# New_rev2.net
KiCad netlist of a schematic drawn in EAGLE
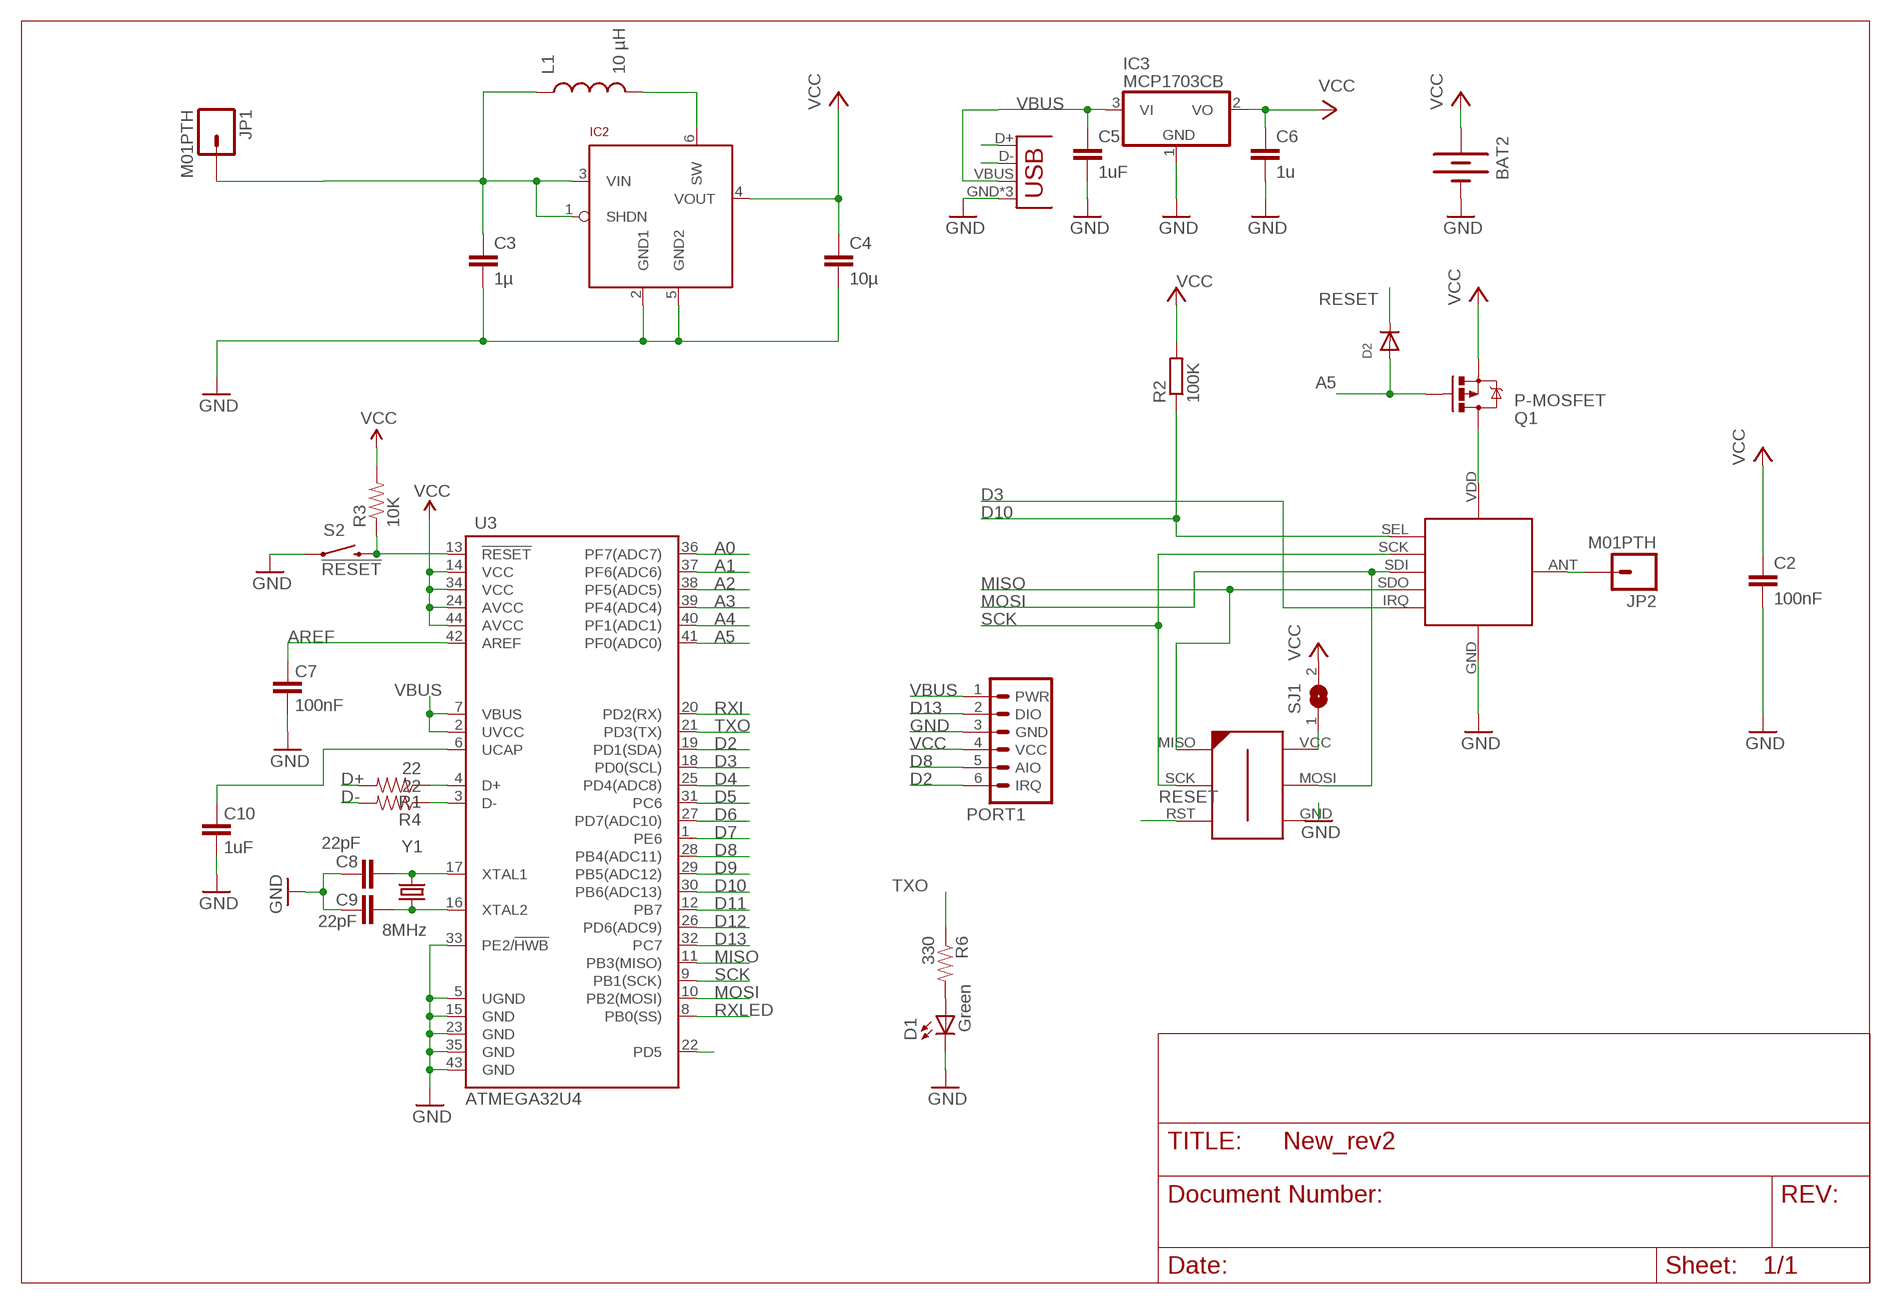
[diagram p0: schematic, sheet 1]

(export (version "E")
  (design (tool "Eeschema 10.0.6"))
  (components
    (comp (ref "BAT2")
      (value "BATTERY20PTH")
      (footprint "eagle-import:BATTCOM_20MM_PTH")
      (libsource (lib "eagle-import") (part "BATTERY20PTH"))
    )
    (comp (ref "C2")
      (value "100nF")
      (footprint "eagle-import:C0603K")
      (libsource (lib "eagle-import") (part "C-EUC0603K"))
    )
    (comp (ref "C3")
      (value "1µ")
      (footprint "eagle-import:0603-CAP")
      (libsource (lib "eagle-import") (part "CAP0603-CAP"))
    )
    (comp (ref "C4")
      (value "10µ")
      (footprint "eagle-import:0805")
      (libsource (lib "eagle-import") (part "CAP0805"))
    )
    (comp (ref "C5")
      (value "1uF")
      (footprint "eagle-import:C0603K")
      (libsource (lib "eagle-import") (part "C-EUC0603K"))
    )
    (comp (ref "C6")
      (value "1u")
      (footprint "eagle-import:C0603K")
      (libsource (lib "eagle-import") (part "C-EUC0603K"))
    )
    (comp (ref "C7")
      (value "100nF")
      (footprint "eagle-import:0402-CAP")
      (libsource (lib "eagle-import") (part "CAP0402-CAP"))
    )
    (comp (ref "C8")
      (value "22pF")
      (footprint "eagle-import:0402-CAP")
      (libsource (lib "eagle-import") (part "CAP0402-CAP"))
    )
    (comp (ref "C9")
      (value "22pF")
      (footprint "eagle-import:0402-CAP")
      (libsource (lib "eagle-import") (part "CAP0402-CAP"))
    )
    (comp (ref "C10")
      (value "1uF")
      (footprint "eagle-import:0402-CAP")
      (libsource (lib "eagle-import") (part "CAP0402-CAP"))
    )
    (comp (ref "D1")
      (value "Green")
      (footprint "eagle-import:LED-0603")
      (libsource (lib "eagle-import") (part "LED0603"))
    )
    (comp (ref "D2")
      (value "DIODESOD-323F")
      (footprint "eagle-import:SOD-323F")
      (libsource (lib "eagle-import") (part "DIODESOD-323F"))
    )
    (comp (ref "IC2")
      (value "LTC3525")
      (footprint "eagle-import:SC70")
      (libsource (lib "eagle-import") (part "LTC3525"))
    )
    (comp (ref "IC3")
      (value "MCP1703CB")
      (footprint "eagle-import:SOT23")
      (libsource (lib "eagle-import") (part "MCP1703CB"))
    )
    (comp (ref "JP1")
      (value "M01PTH")
      (footprint "eagle-import:1X01")
      (libsource (lib "eagle-import") (part "M01PTH"))
    )
    (comp (ref "JP2")
      (value "M01PTH")
      (footprint "eagle-import:1X01")
      (libsource (lib "eagle-import") (part "M01PTH"))
    )
    (comp (ref "JP3")
      (value "USB-MICROB")
      (footprint "eagle-import:USB-MICROB")
      (libsource (lib "eagle-import") (part "USB-MICROB"))
    )
    (comp (ref "L1")
      (value "10 µH")
      (footprint "eagle-import:1210")
      (libsource (lib "eagle-import") (part "INDUCTOR1210"))
    )
    (comp (ref "PORT1")
      (value "JEEPORT-FEMALE")
      (footprint "eagle-import:1X06_FEMALE_LOCK.010")
      (libsource (lib "eagle-import") (part "JEEPORT-FEMALE"))
    )
    (comp (ref "Q1")
      (value "P-MOSFET")
      (footprint "eagle-import:SOT23")
      (libsource (lib "eagle-import") (part "MOSFET-PCHANNEL"))
    )
    (comp (ref "R1")
      (value "22")
      (footprint "eagle-import:0402-RES")
      (libsource (lib "eagle-import") (part "RESISTOR0402-RES"))
    )
    (comp (ref "R2")
      (value "100K")
      (footprint "eagle-import:R0402")
      (libsource (lib "eagle-import") (part "R-EU_R0402"))
    )
    (comp (ref "R3")
      (value "10K")
      (footprint "eagle-import:0402-RES")
      (libsource (lib "eagle-import") (part "RESISTOR0402-RES"))
    )
    (comp (ref "R4")
      (value "22")
      (footprint "eagle-import:0402-RES")
      (libsource (lib "eagle-import") (part "RESISTOR0402-RES"))
    )
    (comp (ref "R6")
      (value "330")
      (footprint "eagle-import:0402-RES")
      (libsource (lib "eagle-import") (part "RESISTOR0402-RES"))
    )
    (comp (ref "RFM12B1")
      (value "RFM12B_MINPADS")
      (footprint "eagle-import:RFM12B-MINPADS")
      (libsource (lib "eagle-import") (part "RFM12B_MINPADS"))
    )
    (comp (ref "S2")
      (value "!RESET")
      (footprint "eagle-import:TACTILE_SWITCH_SMD")
      (libsource (lib "eagle-import") (part "SWITCH-MOMENTARY-2SMD"))
    )
    (comp (ref "SJ1") (value "SJ") (footprint "eagle-import:SJ") (libsource (lib "eagle-import") (part "SJ")))
    (comp (ref "U$2")
      (value "AVR-ISP-6-EDGE")
      (footprint "eagle-import:6PAD_ISP")
      (libsource (lib "eagle-import") (part "AVR-ISP-6-EDGE"))
    )
    (comp (ref "U3")
      (value "ATMEGA32U4")
      (footprint "eagle-import:QFN-44-NOPAD")
      (libsource (lib "eagle-import") (part "ATMEGA32U4QFN2"))
    )
    (comp (ref "Y1")
      (value "8MHz")
      (footprint "eagle-import:CRYSTAL-SMD-5X3")
      (libsource (lib "eagle-import") (part "CRYSTAL5X3"))
    )
  )
  (nets
    (net (code "1") (name "/A0") (class "Default")
      (node (ref "U3") (pin "36") (pinfunction "PF7(ADC7)_36") (pintype "bidirectional"))
    )
    (net (code "2") (name "/A1") (class "Default")
      (node (ref "U3") (pin "37") (pinfunction "PF6(ADC6)_37") (pintype "bidirectional"))
    )
    (net (code "3") (name "/A2") (class "Default")
      (node (ref "U3") (pin "38") (pinfunction "PF5(ADC5)_38") (pintype "bidirectional"))
    )
    (net (code "4") (name "/A3") (class "Default")
      (node (ref "U3") (pin "39") (pinfunction "PF4(ADC4)_39") (pintype "bidirectional"))
    )
    (net (code "5") (name "/A4") (class "Default")
      (node (ref "U3") (pin "40") (pinfunction "PF1(ADC1)_40") (pintype "bidirectional"))
    )
    (net (code "6") (name "/A5") (class "Default")
      (node (ref "D2") (pin "A") (pinfunction "A_A") (pintype "passive"))
      (node (ref "Q1") (pin "1") (pinfunction "G_1") (pintype "passive"))
      (node (ref "U3") (pin "41") (pinfunction "PF0(ADC0)_41") (pintype "bidirectional"))
    )
    (net (code "7") (name "/AREF") (class "Default")
      (node (ref "C7") (pin "2") (pinfunction "2_2") (pintype "passive"))
      (node (ref "U3") (pin "42") (pinfunction "AREF_42") (pintype "bidirectional"))
    )
    (net (code "8") (name "/D+") (class "Default")
      (node (ref "JP3") (pin "D+") (pinfunction "D+_D+") (pintype "bidirectional"))
      (node (ref "R1") (pin "2") (pinfunction "2_2") (pintype "passive"))
    )
    (net (code "9") (name "/D-") (class "Default")
      (node (ref "JP3") (pin "D-") (pinfunction "D-_D-") (pintype "bidirectional"))
      (node (ref "R4") (pin "2") (pinfunction "2_2") (pintype "passive"))
    )
    (net (code "10") (name "/D2") (class "Default")
      (node (ref "PORT1") (pin "6") (pinfunction "IRQ_6") (pintype "bidirectional"))
      (node (ref "U3") (pin "19") (pinfunction "PD1(SDA)_19") (pintype "bidirectional"))
    )
    (net (code "11") (name "/D3") (class "Default")
      (node (ref "RFM12B1") (pin "IRQ") (pinfunction "IRQ_IRQ") (pintype "bidirectional"))
      (node (ref "U3") (pin "18") (pinfunction "PD0(SCL)_18") (pintype "bidirectional"))
    )
    (net (code "12") (name "/D4") (class "Default")
      (node (ref "U3") (pin "25") (pinfunction "PD4(ADC8)_25") (pintype "bidirectional"))
    )
    (net (code "13") (name "/D5") (class "Default")
      (node (ref "U3") (pin "31") (pinfunction "PC6_31") (pintype "bidirectional"))
    )
    (net (code "14") (name "/D6") (class "Default")
      (node (ref "U3") (pin "27") (pinfunction "PD7(ADC10)_27") (pintype "bidirectional"))
    )
    (net (code "15") (name "/D7") (class "Default")
      (node (ref "U3") (pin "1") (pinfunction "PE6_1") (pintype "bidirectional"))
    )
    (net (code "16") (name "/D8") (class "Default")
      (node (ref "PORT1") (pin "5") (pinfunction "AIO_5") (pintype "bidirectional"))
      (node (ref "U3") (pin "28") (pinfunction "PB4(ADC11)_28") (pintype "bidirectional"))
    )
    (net (code "17") (name "/D9") (class "Default")
      (node (ref "U3") (pin "29") (pinfunction "PB5(ADC12)_29") (pintype "bidirectional"))
    )
    (net (code "18") (name "/D10") (class "Default")
      (node (ref "R2") (pin "1") (pinfunction "1_1") (pintype "passive"))
      (node (ref "RFM12B1") (pin "SEL") (pinfunction "SEL_SEL") (pintype "bidirectional"))
      (node (ref "U3") (pin "30") (pinfunction "PB6(ADC13)_30") (pintype "bidirectional"))
    )
    (net (code "19") (name "/D11") (class "Default")
      (node (ref "U3") (pin "12") (pinfunction "PB7_12") (pintype "bidirectional"))
    )
    (net (code "20") (name "/D12") (class "Default")
      (node (ref "U3") (pin "26") (pinfunction "PD6(ADC9)_26") (pintype "bidirectional"))
    )
    (net (code "21") (name "/D13") (class "Default")
      (node (ref "PORT1") (pin "2") (pinfunction "DIO_2") (pintype "bidirectional"))
      (node (ref "U3") (pin "32") (pinfunction "PC7_32") (pintype "bidirectional"))
    )
    (net (code "22") (name "/MISO") (class "Default")
      (node (ref "RFM12B1") (pin "SDO") (pinfunction "SDO/MISO_SDO") (pintype "bidirectional"))
      (node (ref "U$2") (pin "MISO") (pinfunction "P$1_MISO") (pintype "bidirectional"))
      (node (ref "U3") (pin "11") (pinfunction "PB3(MISO)_11") (pintype "bidirectional"))
    )
    (net (code "23") (name "/MOSI") (class "Default")
      (node (ref "RFM12B1") (pin "SDI") (pinfunction "SDI/MOSI_SDI") (pintype "bidirectional"))
      (node (ref "U$2") (pin "MOSI") (pinfunction "P$5_MOSI") (pintype "bidirectional"))
      (node (ref "U3") (pin "10") (pinfunction "PB2(MOSI)_10") (pintype "bidirectional"))
    )
    (net (code "24") (name "/RESET") (class "Default")
      (node (ref "D2") (pin "C") (pinfunction "C_C") (pintype "passive"))
      (node (ref "R3") (pin "1") (pinfunction "1_1") (pintype "passive"))
      (node (ref "S2") (pin "3") (pinfunction "2_3") (pintype "passive"))
      (node (ref "U$2") (pin "RST") (pinfunction "P$3_RST") (pintype "bidirectional"))
      (node (ref "U3") (pin "13") (pinfunction "~{RESET}_13") (pintype "bidirectional"))
    )
    (net (code "25") (name "/RXI") (class "Default")
      (node (ref "U3") (pin "20") (pinfunction "PD2(RX)_20") (pintype "bidirectional"))
    )
    (net (code "26") (name "/RXLED") (class "Default")
      (node (ref "U3") (pin "8") (pinfunction "PB0(SS)_8") (pintype "bidirectional"))
    )
    (net (code "27") (name "/SCK") (class "Default")
      (node (ref "RFM12B1") (pin "SCK") (pinfunction "SCK_SCK") (pintype "bidirectional"))
      (node (ref "U$2") (pin "SCK") (pinfunction "P$2_SCK") (pintype "bidirectional"))
      (node (ref "U3") (pin "9") (pinfunction "PB1(SCK)_9") (pintype "bidirectional"))
    )
    (net (code "28") (name "/TXO") (class "Default")
      (node (ref "R6") (pin "1") (pinfunction "1_1") (pintype "passive"))
      (node (ref "U3") (pin "21") (pinfunction "PD3(TX)_21") (pintype "bidirectional"))
    )
    (net (code "29") (name "/VBUS") (class "Default")
      (node (ref "C5") (pin "1") (pinfunction "1_1") (pintype "passive"))
      (node (ref "IC3") (pin "3") (pinfunction "VI_3") (pintype "input"))
      (node (ref "JP3") (pin "VBUS") (pinfunction "VBUS_VBUS") (pintype "bidirectional"))
      (node (ref "PORT1") (pin "1") (pinfunction "PWR_1") (pintype "power_in"))
      (node (ref "U3") (pin "2") (pinfunction "UVCC_2") (pintype "bidirectional"))
      (node (ref "U3") (pin "7") (pinfunction "VBUS_7") (pintype "bidirectional"))
    )
    (net (code "30") (name "GND") (class "Default")
      (node (ref "BAT2") (pin "2") (pinfunction "-_2") (pintype "power_in"))
      (node (ref "C10") (pin "1") (pinfunction "1_1") (pintype "passive"))
      (node (ref "C2") (pin "2") (pinfunction "2_2") (pintype "passive"))
      (node (ref "C3") (pin "2") (pinfunction "2_2") (pintype "passive"))
      (node (ref "C4") (pin "2") (pinfunction "2_2") (pintype "passive"))
      (node (ref "C5") (pin "2") (pinfunction "2_2") (pintype "passive"))
      (node (ref "C6") (pin "2") (pinfunction "2_2") (pintype "passive"))
      (node (ref "C7") (pin "1") (pinfunction "1_1") (pintype "passive"))
      (node (ref "C8") (pin "2") (pinfunction "2_2") (pintype "passive"))
      (node (ref "C9") (pin "2") (pinfunction "2_2") (pintype "passive"))
      (node (ref "D1") (pin "C") (pinfunction "C_C") (pintype "passive"))
      (node (ref "IC2") (pin "2") (pinfunction "GND1_2") (pintype "power_in"))
      (node (ref "IC2") (pin "5") (pinfunction "GND2_5") (pintype "power_in"))
      (node (ref "IC3") (pin "1") (pinfunction "GND_1") (pintype "passive"))
      (node (ref "JP3") (pin "GND") (pinfunction "GND_GND") (pintype "bidirectional"))
      (node (ref "JP3") (pin "MT1") (pinfunction "GND_MT1") (pintype "bidirectional"))
      (node (ref "JP3") (pin "MT2") (pinfunction "GND_MT2") (pintype "bidirectional"))
      (node (ref "PORT1") (pin "3") (pinfunction "GND_3") (pintype "power_in"))
      (node (ref "RFM12B1") (pin "GND") (pinfunction "GND_GND") (pintype "bidirectional"))
      (node (ref "S2") (pin "1") (pinfunction "1_1") (pintype "passive"))
      (node (ref "U$2") (pin "GND") (pinfunction "P$4_GND") (pintype "bidirectional"))
      (node (ref "U3") (pin "15") (pinfunction "GND_15") (pintype "bidirectional"))
      (node (ref "U3") (pin "23") (pinfunction "GND_23") (pintype "bidirectional"))
      (node (ref "U3") (pin "33") (pinfunction "PE2/~{HWB}_33") (pintype "bidirectional"))
      (node (ref "U3") (pin "35") (pinfunction "GND_35") (pintype "bidirectional"))
      (node (ref "U3") (pin "43") (pinfunction "GND_43") (pintype "bidirectional"))
      (node (ref "U3") (pin "5") (pinfunction "UGND_5") (pintype "bidirectional"))
    )
    (net (code "31") (name "Net-(D1-PadA)") (class "Default")
      (node (ref "D1") (pin "A") (pinfunction "A_A") (pintype "passive"))
      (node (ref "R6") (pin "2") (pinfunction "2_2") (pintype "passive"))
    )
    (net (code "32") (name "Net-(IC2-SHDN)") (class "Default")
      (node (ref "C3") (pin "1") (pinfunction "1_1") (pintype "passive"))
      (node (ref "IC2") (pin "1") (pinfunction "SHDN_1") (pintype "input"))
      (node (ref "IC2") (pin "3") (pinfunction "VIN_3") (pintype "tri_state"))
      (node (ref "JP1") (pin "1") (pinfunction "1_1") (pintype "passive"))
      (node (ref "L1") (pin "1") (pinfunction "1_1") (pintype "passive"))
    )
    (net (code "33") (name "Net-(IC2-SW)") (class "Default")
      (node (ref "IC2") (pin "6") (pinfunction "SW_6") (pintype "power_in"))
      (node (ref "L1") (pin "2") (pinfunction "2_2") (pintype "passive"))
    )
    (net (code "34") (name "Net-(JP2-Pad1)") (class "Default")
      (node (ref "JP2") (pin "1") (pinfunction "1_1") (pintype "passive"))
      (node (ref "RFM12B1") (pin "ANT") (pinfunction "ANT_ANT") (pintype "bidirectional"))
    )
    (net (code "35") (name "Net-(Q1-D)") (class "Default")
      (node (ref "Q1") (pin "3") (pinfunction "D_3") (pintype "passive"))
      (node (ref "RFM12B1") (pin "VDD") (pinfunction "VDD_VDD") (pintype "bidirectional"))
    )
    (net (code "36") (name "Net-(U$2-P$6)") (class "Default")
      (node (ref "SJ1") (pin "1") (pinfunction "1_1") (pintype "passive"))
      (node (ref "U$2") (pin "VCC") (pinfunction "P$6_VCC") (pintype "bidirectional"))
    )
    (net (code "37") (name "Net-(U3-D+)") (class "Default")
      (node (ref "R1") (pin "1") (pinfunction "1_1") (pintype "passive"))
      (node (ref "U3") (pin "4") (pinfunction "D+_4") (pintype "bidirectional"))
    )
    (net (code "38") (name "Net-(U3-D-)") (class "Default")
      (node (ref "R4") (pin "1") (pinfunction "1_1") (pintype "passive"))
      (node (ref "U3") (pin "3") (pinfunction "D-_3") (pintype "bidirectional"))
    )
    (net (code "39") (name "Net-(U3-UCAP)") (class "Default")
      (node (ref "C10") (pin "2") (pinfunction "2_2") (pintype "passive"))
      (node (ref "U3") (pin "6") (pinfunction "UCAP_6") (pintype "bidirectional"))
    )
    (net (code "40") (name "Net-(U3-XTAL1)") (class "Default")
      (node (ref "C8") (pin "1") (pinfunction "1_1") (pintype "passive"))
      (node (ref "U3") (pin "17") (pinfunction "XTAL1_17") (pintype "bidirectional"))
      (node (ref "Y1") (pin "3") (pinfunction "2_3") (pintype "passive"))
    )
    (net (code "41") (name "Net-(U3-XTAL2)") (class "Default")
      (node (ref "C9") (pin "1") (pinfunction "1_1") (pintype "passive"))
      (node (ref "U3") (pin "16") (pinfunction "XTAL2_16") (pintype "bidirectional"))
      (node (ref "Y1") (pin "1") (pinfunction "1_1") (pintype "passive"))
    )
    (net (code "42") (name "VCC") (class "Default")
      (node (ref "BAT2") (pin "1") (pinfunction "+_1") (pintype "power_in"))
      (node (ref "C2") (pin "1") (pinfunction "1_1") (pintype "passive"))
      (node (ref "C4") (pin "1") (pinfunction "1_1") (pintype "passive"))
      (node (ref "C6") (pin "1") (pinfunction "1_1") (pintype "passive"))
      (node (ref "IC2") (pin "4") (pinfunction "VOUT_4") (pintype "power_in"))
      (node (ref "IC3") (pin "2") (pinfunction "VO_2") (pintype "passive"))
      (node (ref "PORT1") (pin "4") (pinfunction "VCC_4") (pintype "power_in"))
      (node (ref "Q1") (pin "2") (pinfunction "S_2") (pintype "passive"))
      (node (ref "R2") (pin "2") (pinfunction "2_2") (pintype "passive"))
      (node (ref "R3") (pin "2") (pinfunction "2_2") (pintype "passive"))
      (node (ref "SJ1") (pin "2") (pinfunction "2_2") (pintype "passive"))
      (node (ref "U3") (pin "14") (pinfunction "VCC_14") (pintype "bidirectional"))
      (node (ref "U3") (pin "24") (pinfunction "AVCC_24") (pintype "bidirectional"))
      (node (ref "U3") (pin "34") (pinfunction "VCC_34") (pintype "bidirectional"))
      (node (ref "U3") (pin "44") (pinfunction "AVCC_44") (pintype "bidirectional"))
    )
    (net (code "43") (name "unconnected-(U3-PD5-Pad22)") (class "Default")
      (node (ref "U3") (pin "22") (pinfunction "PD5_22") (pintype "bidirectional"))
    )
  )
)
